# UV_LED_Lamp.net
KiCad netlist of a schematic drawn in EAGLE
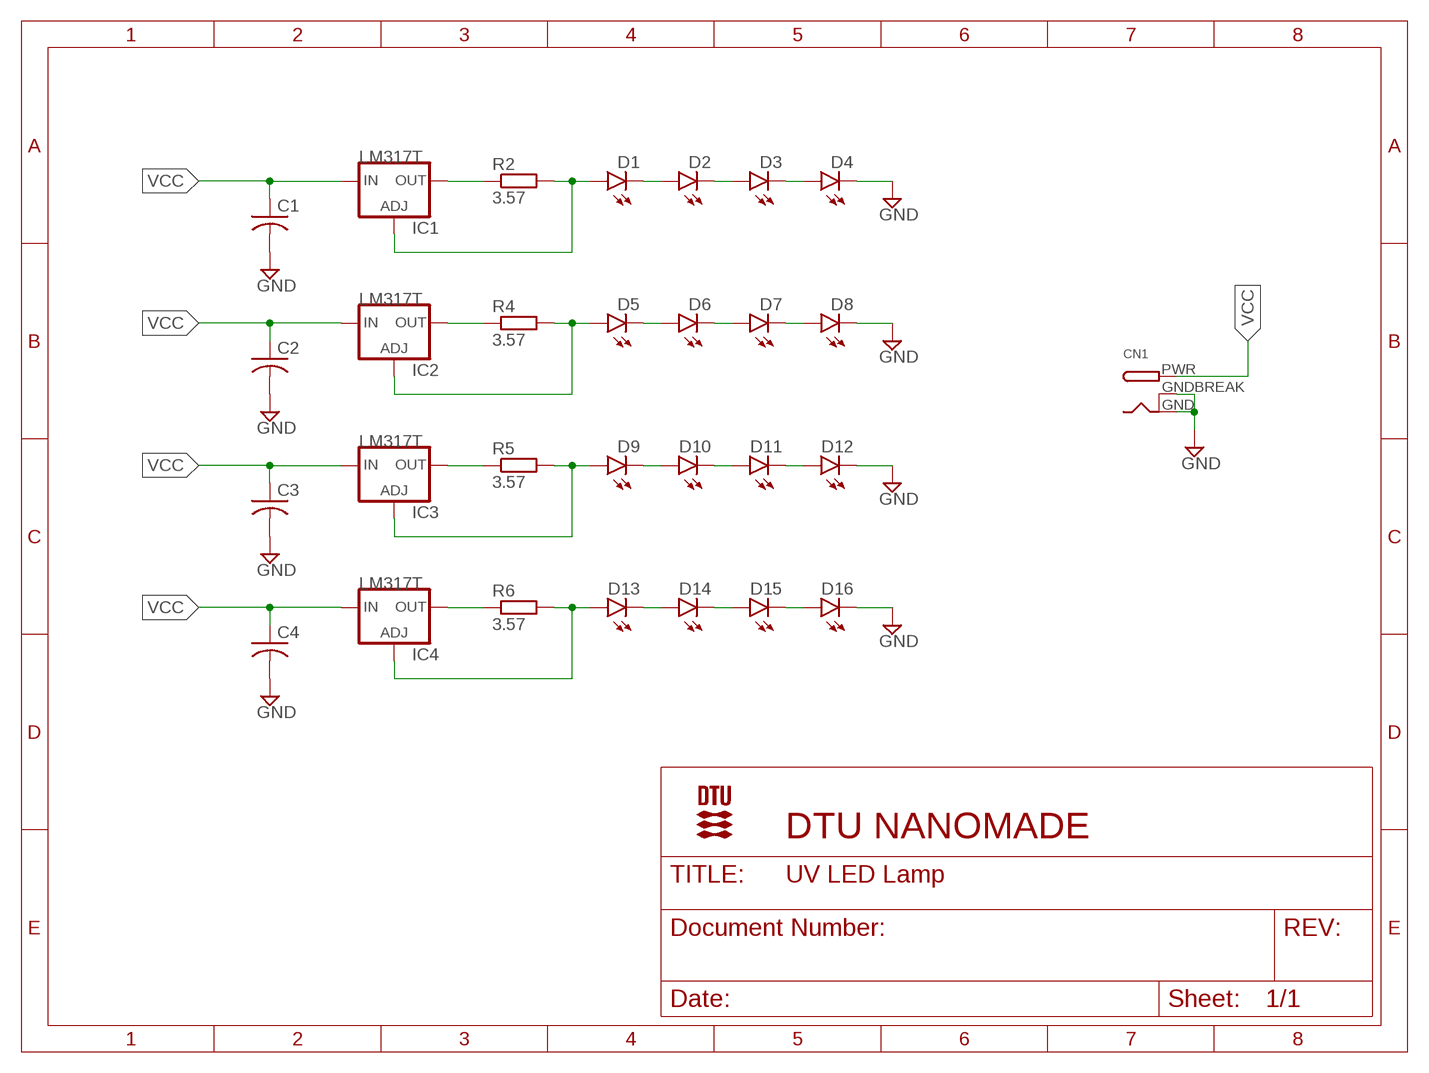
[diagram p0: schematic, sheet 1]

(export (version "E")
  (design (tool "Eeschema 10.0.6"))
  (components
    (comp (ref "C1")
      (value "C-USC0805K")
      (footprint "eagle-import:C0805K")
      (libsource (lib "eagle-import") (part "C-USC0805K"))
    )
    (comp (ref "C2")
      (value "C-USC0805K")
      (footprint "eagle-import:C0805K")
      (libsource (lib "eagle-import") (part "C-USC0805K"))
    )
    (comp (ref "C3")
      (value "C-USC0805K")
      (footprint "eagle-import:C0805K")
      (libsource (lib "eagle-import") (part "C-USC0805K"))
    )
    (comp (ref "C4")
      (value "C-USC0805K")
      (footprint "eagle-import:C0805K")
      (libsource (lib "eagle-import") (part "C-USC0805K"))
    )
    (comp (ref "CN1")
      (value "DCBARRELPTH")
      (footprint "eagle-import:DCJACK_2MM_PTH")
      (libsource (lib "eagle-import") (part "DCBARRELPTH"))
    )
    (comp (ref "D1")
      (value "PM2L-1LLE-LC")
      (footprint "eagle-import:PM2L-1LLE-LC")
      (libsource (lib "eagle-import") (part "PM2L-1LLE-LC"))
    )
    (comp (ref "D2")
      (value "PM2L-1LLE-LC")
      (footprint "eagle-import:PM2L-1LLE-LC")
      (libsource (lib "eagle-import") (part "PM2L-1LLE-LC"))
    )
    (comp (ref "D3")
      (value "PM2L-1LLE-LC")
      (footprint "eagle-import:PM2L-1LLE-LC")
      (libsource (lib "eagle-import") (part "PM2L-1LLE-LC"))
    )
    (comp (ref "D4")
      (value "PM2L-1LLE-LC")
      (footprint "eagle-import:PM2L-1LLE-LC")
      (libsource (lib "eagle-import") (part "PM2L-1LLE-LC"))
    )
    (comp (ref "D5")
      (value "PM2L-1LLE-LC")
      (footprint "eagle-import:PM2L-1LLE-LC")
      (libsource (lib "eagle-import") (part "PM2L-1LLE-LC"))
    )
    (comp (ref "D6")
      (value "PM2L-1LLE-LC")
      (footprint "eagle-import:PM2L-1LLE-LC")
      (libsource (lib "eagle-import") (part "PM2L-1LLE-LC"))
    )
    (comp (ref "D7")
      (value "PM2L-1LLE-LC")
      (footprint "eagle-import:PM2L-1LLE-LC")
      (libsource (lib "eagle-import") (part "PM2L-1LLE-LC"))
    )
    (comp (ref "D8")
      (value "PM2L-1LLE-LC")
      (footprint "eagle-import:PM2L-1LLE-LC")
      (libsource (lib "eagle-import") (part "PM2L-1LLE-LC"))
    )
    (comp (ref "D9")
      (value "PM2L-1LLE-LC")
      (footprint "eagle-import:PM2L-1LLE-LC")
      (libsource (lib "eagle-import") (part "PM2L-1LLE-LC"))
    )
    (comp (ref "D10")
      (value "PM2L-1LLE-LC")
      (footprint "eagle-import:PM2L-1LLE-LC")
      (libsource (lib "eagle-import") (part "PM2L-1LLE-LC"))
    )
    (comp (ref "D11")
      (value "PM2L-1LLE-LC")
      (footprint "eagle-import:PM2L-1LLE-LC")
      (libsource (lib "eagle-import") (part "PM2L-1LLE-LC"))
    )
    (comp (ref "D12")
      (value "PM2L-1LLE-LC")
      (footprint "eagle-import:PM2L-1LLE-LC")
      (libsource (lib "eagle-import") (part "PM2L-1LLE-LC"))
    )
    (comp (ref "D13")
      (value "PM2L-1LLE-LC")
      (footprint "eagle-import:PM2L-1LLE-LC")
      (libsource (lib "eagle-import") (part "PM2L-1LLE-LC"))
    )
    (comp (ref "D14")
      (value "PM2L-1LLE-LC")
      (footprint "eagle-import:PM2L-1LLE-LC")
      (libsource (lib "eagle-import") (part "PM2L-1LLE-LC"))
    )
    (comp (ref "D15")
      (value "PM2L-1LLE-LC")
      (footprint "eagle-import:PM2L-1LLE-LC")
      (libsource (lib "eagle-import") (part "PM2L-1LLE-LC"))
    )
    (comp (ref "D16")
      (value "PM2L-1LLE-LC")
      (footprint "eagle-import:PM2L-1LLE-LC")
      (libsource (lib "eagle-import") (part "PM2L-1LLE-LC"))
    )
    (comp (ref "IC1")
      (value "LM317T")
      (footprint "eagle-import:317TL")
      (libsource (lib "eagle-import") (part "LM317TL"))
    )
    (comp (ref "IC2")
      (value "LM317T")
      (footprint "eagle-import:317TL")
      (libsource (lib "eagle-import") (part "LM317TL"))
    )
    (comp (ref "IC3")
      (value "LM317T")
      (footprint "eagle-import:317TL")
      (libsource (lib "eagle-import") (part "LM317TL"))
    )
    (comp (ref "IC4")
      (value "LM317T")
      (footprint "eagle-import:317TL")
      (libsource (lib "eagle-import") (part "LM317TL"))
    )
    (comp (ref "R2")
      (value "3.57")
      (footprint "eagle-import:0207_7")
      (libsource (lib "eagle-import") (part "R-EU_0207/7"))
    )
    (comp (ref "R4")
      (value "3.57")
      (footprint "eagle-import:0207_7")
      (libsource (lib "eagle-import") (part "R-EU_0207/7"))
    )
    (comp (ref "R5")
      (value "3.57")
      (footprint "eagle-import:0207_7")
      (libsource (lib "eagle-import") (part "R-EU_0207/7"))
    )
    (comp (ref "R6")
      (value "3.57")
      (footprint "eagle-import:0207_7")
      (libsource (lib "eagle-import") (part "R-EU_0207/7"))
    )
    (comp (ref "U$1")
      (value "DTU_LOGO")
      (footprint "eagle-import:DTU_LOGO")
      (libsource (lib "eagle-import") (part "DTU_LOGO"))
    )
    (comp (ref "U$2")
      (value "DTU_LOGO")
      (footprint "eagle-import:DTU_LOGO")
      (libsource (lib "eagle-import") (part "DTU_LOGO"))
    )
  )
  (nets
    (net (code "1") (name "GND") (class "Default")
      (node (ref "C1") (pin "2") (pinfunction "2_2") (pintype "passive"))
      (node (ref "C2") (pin "2") (pinfunction "2_2") (pintype "passive"))
      (node (ref "C3") (pin "2") (pinfunction "2_2") (pintype "passive"))
      (node (ref "C4") (pin "2") (pinfunction "2_2") (pintype "passive"))
      (node (ref "CN1") (pin "GND") (pinfunction "GND_GND") (pintype "power_in"))
      (node (ref "CN1") (pin "GNDBREAK") (pinfunction "GNDBREAK_GNDBREAK") (pintype "power_in"))
      (node (ref "D12") (pin "P$1") (pinfunction "C_P$1") (pintype "passive"))
      (node (ref "D16") (pin "P$1") (pinfunction "C_P$1") (pintype "passive"))
      (node (ref "D4") (pin "P$1") (pinfunction "C_P$1") (pintype "passive"))
      (node (ref "D8") (pin "P$1") (pinfunction "C_P$1") (pintype "passive"))
    )
    (net (code "2") (name "Net-(D1-A)") (class "Default")
      (node (ref "D1") (pin "P$2") (pinfunction "A_P$2") (pintype "passive"))
      (node (ref "IC1") (pin "1") (pinfunction "ADJ_1") (pintype "input"))
      (node (ref "R2") (pin "2") (pinfunction "2_2") (pintype "passive"))
    )
    (net (code "3") (name "Net-(D1-C)") (class "Default")
      (node (ref "D1") (pin "P$1") (pinfunction "C_P$1") (pintype "passive"))
      (node (ref "D2") (pin "P$2") (pinfunction "A_P$2") (pintype "passive"))
    )
    (net (code "4") (name "Net-(D2-C)") (class "Default")
      (node (ref "D2") (pin "P$1") (pinfunction "C_P$1") (pintype "passive"))
      (node (ref "D3") (pin "P$2") (pinfunction "A_P$2") (pintype "passive"))
    )
    (net (code "5") (name "Net-(D3-C)") (class "Default")
      (node (ref "D3") (pin "P$1") (pinfunction "C_P$1") (pintype "passive"))
      (node (ref "D4") (pin "P$2") (pinfunction "A_P$2") (pintype "passive"))
    )
    (net (code "6") (name "Net-(D5-A)") (class "Default")
      (node (ref "D5") (pin "P$2") (pinfunction "A_P$2") (pintype "passive"))
      (node (ref "IC2") (pin "1") (pinfunction "ADJ_1") (pintype "input"))
      (node (ref "R4") (pin "2") (pinfunction "2_2") (pintype "passive"))
    )
    (net (code "7") (name "Net-(D5-C)") (class "Default")
      (node (ref "D5") (pin "P$1") (pinfunction "C_P$1") (pintype "passive"))
      (node (ref "D6") (pin "P$2") (pinfunction "A_P$2") (pintype "passive"))
    )
    (net (code "8") (name "Net-(D6-C)") (class "Default")
      (node (ref "D6") (pin "P$1") (pinfunction "C_P$1") (pintype "passive"))
      (node (ref "D7") (pin "P$2") (pinfunction "A_P$2") (pintype "passive"))
    )
    (net (code "9") (name "Net-(D7-C)") (class "Default")
      (node (ref "D7") (pin "P$1") (pinfunction "C_P$1") (pintype "passive"))
      (node (ref "D8") (pin "P$2") (pinfunction "A_P$2") (pintype "passive"))
    )
    (net (code "10") (name "Net-(D9-A)") (class "Default")
      (node (ref "D9") (pin "P$2") (pinfunction "A_P$2") (pintype "passive"))
      (node (ref "IC3") (pin "1") (pinfunction "ADJ_1") (pintype "input"))
      (node (ref "R5") (pin "2") (pinfunction "2_2") (pintype "passive"))
    )
    (net (code "11") (name "Net-(D10-A)") (class "Default")
      (node (ref "D10") (pin "P$2") (pinfunction "A_P$2") (pintype "passive"))
      (node (ref "D9") (pin "P$1") (pinfunction "C_P$1") (pintype "passive"))
    )
    (net (code "12") (name "Net-(D10-C)") (class "Default")
      (node (ref "D10") (pin "P$1") (pinfunction "C_P$1") (pintype "passive"))
      (node (ref "D11") (pin "P$2") (pinfunction "A_P$2") (pintype "passive"))
    )
    (net (code "13") (name "Net-(D11-C)") (class "Default")
      (node (ref "D11") (pin "P$1") (pinfunction "C_P$1") (pintype "passive"))
      (node (ref "D12") (pin "P$2") (pinfunction "A_P$2") (pintype "passive"))
    )
    (net (code "14") (name "Net-(D13-A)") (class "Default")
      (node (ref "D13") (pin "P$2") (pinfunction "A_P$2") (pintype "passive"))
      (node (ref "IC4") (pin "1") (pinfunction "ADJ_1") (pintype "input"))
      (node (ref "R6") (pin "2") (pinfunction "2_2") (pintype "passive"))
    )
    (net (code "15") (name "Net-(D13-C)") (class "Default")
      (node (ref "D13") (pin "P$1") (pinfunction "C_P$1") (pintype "passive"))
      (node (ref "D14") (pin "P$2") (pinfunction "A_P$2") (pintype "passive"))
    )
    (net (code "16") (name "Net-(D14-C)") (class "Default")
      (node (ref "D14") (pin "P$1") (pinfunction "C_P$1") (pintype "passive"))
      (node (ref "D15") (pin "P$2") (pinfunction "A_P$2") (pintype "passive"))
    )
    (net (code "17") (name "Net-(D15-C)") (class "Default")
      (node (ref "D15") (pin "P$1") (pinfunction "C_P$1") (pintype "passive"))
      (node (ref "D16") (pin "P$2") (pinfunction "A_P$2") (pintype "passive"))
    )
    (net (code "18") (name "Net-(IC1-OUT)") (class "Default")
      (node (ref "IC1") (pin "2") (pinfunction "OUT_2") (pintype "passive"))
      (node (ref "R2") (pin "1") (pinfunction "1_1") (pintype "passive"))
    )
    (net (code "19") (name "Net-(IC2-OUT)") (class "Default")
      (node (ref "IC2") (pin "2") (pinfunction "OUT_2") (pintype "passive"))
      (node (ref "R4") (pin "1") (pinfunction "1_1") (pintype "passive"))
    )
    (net (code "20") (name "Net-(IC3-OUT)") (class "Default")
      (node (ref "IC3") (pin "2") (pinfunction "OUT_2") (pintype "passive"))
      (node (ref "R5") (pin "1") (pinfunction "1_1") (pintype "passive"))
    )
    (net (code "21") (name "Net-(IC4-OUT)") (class "Default")
      (node (ref "IC4") (pin "2") (pinfunction "OUT_2") (pintype "passive"))
      (node (ref "R6") (pin "1") (pinfunction "1_1") (pintype "passive"))
    )
    (net (code "22") (name "VCC") (class "Default")
      (node (ref "C1") (pin "1") (pinfunction "1_1") (pintype "passive"))
      (node (ref "C2") (pin "1") (pinfunction "1_1") (pintype "passive"))
      (node (ref "C3") (pin "1") (pinfunction "1_1") (pintype "passive"))
      (node (ref "C4") (pin "1") (pinfunction "1_1") (pintype "passive"))
      (node (ref "CN1") (pin "PWR") (pinfunction "PWR_PWR") (pintype "power_in"))
      (node (ref "IC1") (pin "3") (pinfunction "IN_3") (pintype "input"))
      (node (ref "IC2") (pin "3") (pinfunction "IN_3") (pintype "input"))
      (node (ref "IC3") (pin "3") (pinfunction "IN_3") (pintype "input"))
      (node (ref "IC4") (pin "3") (pinfunction "IN_3") (pintype "input"))
    )
  )
)
